# Grove_-_Serial_MP3_Player.net
KiCad netlist of a schematic drawn in EAGLE
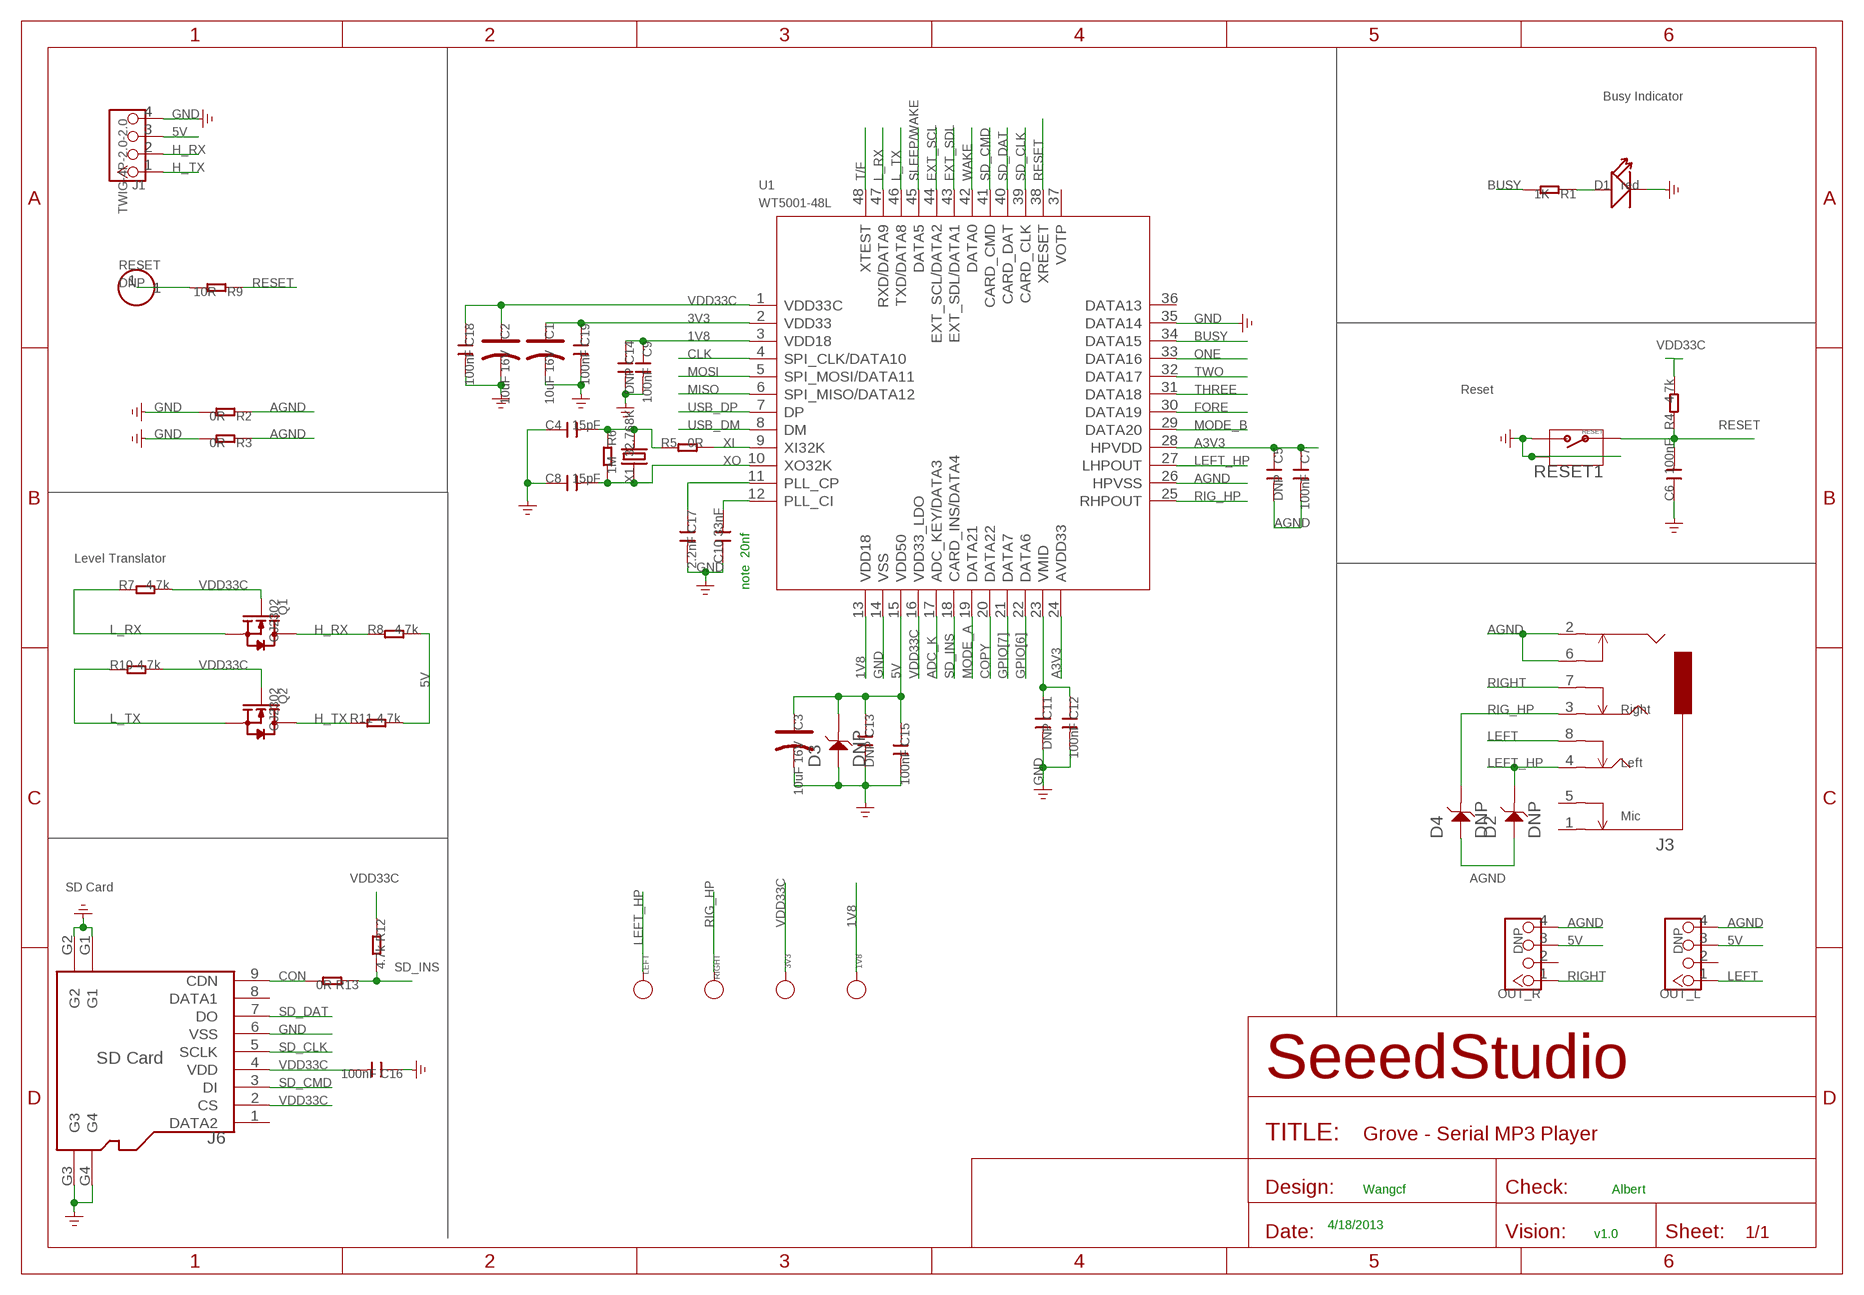
[diagram p0: schematic, sheet 1]

(export (version "E")
  (design (tool "Eeschema 10.0.6"))
  (components
    (comp (ref "1V8")
      (value "PAD-TEST-POINT'4545'")
      (footprint "eagle-import:TP_4545")
      (fields (field (name "PARTNO") "DNP"))
      (libsource (lib "eagle-import") (part "PAD-TEST-POINT'4545'"))
    )
    (comp (ref "3V3")
      (value "PAD-TEST-POINT'4545'")
      (footprint "eagle-import:TP_4545")
      (fields (field (name "PARTNO") "DNP"))
      (libsource (lib "eagle-import") (part "PAD-TEST-POINT'4545'"))
    )
    (comp (ref "C1")
      (value "10uF 16V")
      (footprint "eagle-import:AVX-A")
      (libsource (lib "eagle-import") (part "CAP-AVX-A"))
    )
    (comp (ref "C2")
      (value "10uF 16V")
      (footprint "eagle-import:AVX-A")
      (libsource (lib "eagle-import") (part "CAP-AVX-A"))
    )
    (comp (ref "C3")
      (value "10uF 16V")
      (footprint "eagle-import:AVX-A")
      (libsource (lib "eagle-import") (part "CAP-AVX-A"))
    )
    (comp (ref "C4")
      (value "15pF")
      (footprint "eagle-import:C0603")
      (libsource (lib "eagle-import") (part "C-0603"))
    )
    (comp (ref "C5")
      (value "DNP")
      (footprint "eagle-import:C0805")
      (libsource (lib "eagle-import") (part "C-0805"))
    )
    (comp (ref "C6")
      (value "100nF")
      (footprint "eagle-import:C0603")
      (libsource (lib "eagle-import") (part "C-0603"))
    )
    (comp (ref "C7")
      (value "100nF")
      (footprint "eagle-import:C0603")
      (libsource (lib "eagle-import") (part "C-0603"))
    )
    (comp (ref "C8")
      (value "15pF")
      (footprint "eagle-import:C0603")
      (libsource (lib "eagle-import") (part "C-0603"))
    )
    (comp (ref "C9")
      (value "100nF")
      (footprint "eagle-import:C0603")
      (libsource (lib "eagle-import") (part "C-0603"))
    )
    (comp (ref "C10")
      (value "33nF")
      (footprint "eagle-import:C0603")
      (libsource (lib "eagle-import") (part "C-0603"))
    )
    (comp (ref "C11")
      (value "DNP")
      (footprint "eagle-import:C0805")
      (libsource (lib "eagle-import") (part "C-0805"))
    )
    (comp (ref "C12")
      (value "100nF")
      (footprint "eagle-import:C0603")
      (libsource (lib "eagle-import") (part "C-0603"))
    )
    (comp (ref "C13")
      (value "DNP")
      (footprint "eagle-import:C0805")
      (libsource (lib "eagle-import") (part "C-0805"))
    )
    (comp (ref "C14")
      (value "DNP")
      (footprint "eagle-import:C0805")
      (libsource (lib "eagle-import") (part "C-0805"))
    )
    (comp (ref "C15")
      (value "100nF")
      (footprint "eagle-import:C0603")
      (libsource (lib "eagle-import") (part "C-0603"))
    )
    (comp (ref "C16")
      (value "100nF")
      (footprint "eagle-import:C0603")
      (libsource (lib "eagle-import") (part "C-0603"))
    )
    (comp (ref "C17")
      (value "2.2nF")
      (footprint "eagle-import:C0603")
      (libsource (lib "eagle-import") (part "C-0603"))
    )
    (comp (ref "C18")
      (value "100nF")
      (footprint "eagle-import:C0603")
      (libsource (lib "eagle-import") (part "C-0603"))
    )
    (comp (ref "C19")
      (value "100nF")
      (footprint "eagle-import:C0603")
      (libsource (lib "eagle-import") (part "C-0603"))
    )
    (comp (ref "D1")
      (value "red")
      (footprint "eagle-import:LED-0603")
      (libsource (lib "eagle-import") (part "LED'0603'"))
    )
    (comp (ref "D2")
      (value "DNP")
      (footprint "eagle-import:SOD123-2.7X1.6")
      (libsource (lib "eagle-import") (part "D-ESD-2P'CESD5V0D1'"))
    )
    (comp (ref "D3")
      (value "DNP")
      (footprint "eagle-import:SOD123-2.7X1.6")
      (libsource (lib "eagle-import") (part "D-ESD-2P'CESD5V0D1'"))
    )
    (comp (ref "D4")
      (value "DNP")
      (footprint "eagle-import:SOD123-2.7X1.6")
      (libsource (lib "eagle-import") (part "D-ESD-2P'CESD5V0D1'"))
    )
    (comp (ref "J1")
      (value "TWIG-4P-2.0-2.0")
      (footprint "eagle-import:4P-2.0")
      (libsource (lib "eagle-import") (part "TWIG-4P-2.0-2.0"))
    )
    (comp (ref "J3")
      (value "AUDIO-8P-SMD'PJ-3536-L6S'")
      (footprint "eagle-import:8P-3.5-SMD")
      (libsource (lib "eagle-import") (part "AUDIO-8P-SMD'PJ-3536-L6S'"))
    )
    (comp (ref "J6")
      (value "SD Card")
      (footprint "eagle-import:9P-SMD-W_-RING")
      (libsource (lib "eagle-import") (part "HOLDER-MICROSD-9P"))
    )
    (comp (ref "LEFT")
      (value "PAD-TEST-POINT'4545'")
      (footprint "eagle-import:TP_4545")
      (fields (field (name "PARTNO") "DNP"))
      (libsource (lib "eagle-import") (part "PAD-TEST-POINT'4545'"))
    )
    (comp (ref "OUT_L")
      (value "DNP")
      (footprint "eagle-import:4P-2.0")
      (libsource (lib "eagle-import") (part "TWIG-4P-2.0-2.0"))
    )
    (comp (ref "OUT_R")
      (value "DNP")
      (footprint "eagle-import:4P-2.0")
      (libsource (lib "eagle-import") (part "TWIG-4P-2.0-2.0"))
    )
    (comp (ref "Q1")
      (value "CJ2302")
      (footprint "eagle-import:SOT23")
      (libsource (lib "eagle-import") (part "MOSFET-N'SOT23'"))
    )
    (comp (ref "Q2")
      (value "CJ2302")
      (footprint "eagle-import:SOT23")
      (libsource (lib "eagle-import") (part "MOSFET-N'SOT23'"))
    )
    (comp (ref "R1")
      (value "1K")
      (footprint "eagle-import:R0603")
      (libsource (lib "eagle-import") (part "R-0603"))
    )
    (comp (ref "R2")
      (value "0R")
      (footprint "eagle-import:R0603")
      (libsource (lib "eagle-import") (part "R-0603"))
    )
    (comp (ref "R3")
      (value "0R")
      (footprint "eagle-import:R0603")
      (libsource (lib "eagle-import") (part "R-0603"))
    )
    (comp (ref "R4")
      (value "4.7k")
      (footprint "eagle-import:R0603")
      (libsource (lib "eagle-import") (part "R-0603"))
    )
    (comp (ref "R5")
      (value "0R")
      (footprint "eagle-import:R0603")
      (libsource (lib "eagle-import") (part "R-0603"))
    )
    (comp (ref "R6")
      (value "1M")
      (footprint "eagle-import:R0603")
      (libsource (lib "eagle-import") (part "R-0603"))
    )
    (comp (ref "R7")
      (value "4.7k")
      (footprint "eagle-import:R0603")
      (libsource (lib "eagle-import") (part "R-0603"))
    )
    (comp (ref "R8")
      (value "4.7k")
      (footprint "eagle-import:R0603")
      (libsource (lib "eagle-import") (part "R-0603"))
    )
    (comp (ref "R9")
      (value "10R")
      (footprint "eagle-import:R0603")
      (libsource (lib "eagle-import") (part "R-0603"))
    )
    (comp (ref "R10")
      (value "4.7k")
      (footprint "eagle-import:R0603")
      (libsource (lib "eagle-import") (part "R-0603"))
    )
    (comp (ref "R11")
      (value "4.7k")
      (footprint "eagle-import:R0603")
      (libsource (lib "eagle-import") (part "R-0603"))
    )
    (comp (ref "R12")
      (value "4.7k")
      (footprint "eagle-import:R0603")
      (libsource (lib "eagle-import") (part "R-0603"))
    )
    (comp (ref "R13")
      (value "0R")
      (footprint "eagle-import:R0603")
      (libsource (lib "eagle-import") (part "R-0603"))
    )
    (comp (ref "RESET")
      (value "DNP")
      (footprint "eagle-import:1P-65_35MIL")
      (libsource (lib "eagle-import") (part "HEADER-1P-35"))
    )
    (comp (ref "RESET1")
      (value "RESET")
      (footprint "eagle-import:4P-SMD-7X3.5X3.5H")
      (libsource (lib "eagle-import") (part "BUTTON-4P-REINFORCE'TS-1188E'"))
    )
    (comp (ref "RIGHT")
      (value "PAD-TEST-POINT'4545'")
      (footprint "eagle-import:TP_4545")
      (fields (field (name "PARTNO") "DNP"))
      (libsource (lib "eagle-import") (part "PAD-TEST-POINT'4545'"))
    )
    (comp (ref "U1")
      (value "WT5001-48L")
      (footprint "eagle-import:TQFP48")
      (libsource (lib "eagle-import") (part "WT5001-48L"))
    )
    (comp (ref "X1")
      (value "32.768K")
      (footprint "eagle-import:2P-SMD-3.2X1.5")
      (libsource (lib "eagle-import") (part "CRYSTAL-3215"))
    )
  )
  (nets
    (net (code "1") (name "/1V8") (class "Default")
      (node (ref "1V8") (pin "T") (pinfunction "T_T") (pintype "bidirectional"))
      (node (ref "C14") (pin "1") (pinfunction "1_1") (pintype "passive"))
      (node (ref "C9") (pin "1") (pinfunction "1_1") (pintype "passive"))
      (node (ref "U1") (pin "13") (pinfunction "VDD18_13") (pintype "bidirectional"))
      (node (ref "U1") (pin "3") (pinfunction "VDD18_3") (pintype "bidirectional"))
    )
    (net (code "2") (name "/3V3") (class "Default")
      (node (ref "C1") (pin "+") (pinfunction "+_+") (pintype "passive"))
      (node (ref "C19") (pin "1") (pinfunction "1_1") (pintype "passive"))
      (node (ref "U1") (pin "2") (pinfunction "VDD33_2") (pintype "bidirectional"))
    )
    (net (code "3") (name "/5V") (class "Default")
      (node (ref "C13") (pin "1") (pinfunction "1_1") (pintype "passive"))
      (node (ref "C15") (pin "1") (pinfunction "1_1") (pintype "passive"))
      (node (ref "C3") (pin "+") (pinfunction "+_+") (pintype "passive"))
      (node (ref "D3") (pin "2") (pinfunction "2_2") (pintype "bidirectional"))
      (node (ref "J1") (pin "3") (pinfunction "3_3") (pintype "bidirectional"))
      (node (ref "OUT_L") (pin "3") (pinfunction "3_3") (pintype "bidirectional"))
      (node (ref "OUT_R") (pin "3") (pinfunction "3_3") (pintype "bidirectional"))
      (node (ref "R11") (pin "2") (pinfunction "2_2") (pintype "passive"))
      (node (ref "R8") (pin "2") (pinfunction "2_2") (pintype "passive"))
      (node (ref "U1") (pin "15") (pinfunction "VDD50_15") (pintype "bidirectional"))
    )
    (net (code "4") (name "/A3V3") (class "Default")
      (node (ref "C5") (pin "1") (pinfunction "1_1") (pintype "passive"))
      (node (ref "C7") (pin "1") (pinfunction "1_1") (pintype "passive"))
      (node (ref "U1") (pin "24") (pinfunction "AVDD33_24") (pintype "bidirectional"))
      (node (ref "U1") (pin "28") (pinfunction "HPVDD_28") (pintype "bidirectional"))
    )
    (net (code "5") (name "/ADC_K") (class "Default")
      (node (ref "U1") (pin "17") (pinfunction "ADC_KEY/DATA3_17") (pintype "bidirectional"))
    )
    (net (code "6") (name "/AGND") (class "Default")
      (node (ref "C5") (pin "2") (pinfunction "2_2") (pintype "passive"))
      (node (ref "C7") (pin "2") (pinfunction "2_2") (pintype "passive"))
      (node (ref "D2") (pin "1") (pinfunction "1_1") (pintype "bidirectional"))
      (node (ref "D4") (pin "1") (pinfunction "1_1") (pintype "bidirectional"))
      (node (ref "J3") (pin "2") (pinfunction "2_2") (pintype "bidirectional"))
      (node (ref "J3") (pin "6") (pinfunction "6_6") (pintype "bidirectional"))
      (node (ref "OUT_L") (pin "4") (pinfunction "4_4") (pintype "bidirectional"))
      (node (ref "OUT_R") (pin "4") (pinfunction "4_4") (pintype "bidirectional"))
      (node (ref "R2") (pin "1") (pinfunction "1_1") (pintype "passive"))
      (node (ref "R3") (pin "1") (pinfunction "1_1") (pintype "passive"))
      (node (ref "U1") (pin "26") (pinfunction "HPVSS_26") (pintype "bidirectional"))
    )
    (net (code "7") (name "/BUSY") (class "Default")
      (node (ref "R1") (pin "2") (pinfunction "2_2") (pintype "passive"))
      (node (ref "U1") (pin "34") (pinfunction "DATA15_34") (pintype "bidirectional"))
    )
    (net (code "8") (name "/CLK") (class "Default")
      (node (ref "U1") (pin "4") (pinfunction "SPI_CLK/DATA10_4") (pintype "bidirectional"))
    )
    (net (code "9") (name "/CON") (class "Default")
      (node (ref "J6") (pin "9") (pinfunction "CDN_9") (pintype "bidirectional"))
      (node (ref "R13") (pin "2") (pinfunction "2_2") (pintype "passive"))
    )
    (net (code "10") (name "/COPY") (class "Default")
      (node (ref "U1") (pin "20") (pinfunction "DATA22_20") (pintype "bidirectional"))
    )
    (net (code "11") (name "/EXT_SCL") (class "Default")
      (node (ref "U1") (pin "44") (pinfunction "EXT_SCL/DATA2_44") (pintype "bidirectional"))
    )
    (net (code "12") (name "/EXT_SDL") (class "Default")
      (node (ref "U1") (pin "43") (pinfunction "EXT_SDL/DATA1_43") (pintype "bidirectional"))
    )
    (net (code "13") (name "/FORE") (class "Default")
      (node (ref "U1") (pin "30") (pinfunction "DATA19_30") (pintype "bidirectional"))
    )
    (net (code "14") (name "/GPIO[6]") (class "Default")
      (node (ref "U1") (pin "22") (pinfunction "DATA6_22") (pintype "bidirectional"))
    )
    (net (code "15") (name "/GPIO[7]") (class "Default")
      (node (ref "U1") (pin "21") (pinfunction "DATA7_21") (pintype "bidirectional"))
    )
    (net (code "16") (name "/H_RX") (class "Default")
      (node (ref "J1") (pin "2") (pinfunction "2_2") (pintype "bidirectional"))
      (node (ref "Q1") (pin "3") (pinfunction "D_3") (pintype "passive"))
      (node (ref "R8") (pin "1") (pinfunction "1_1") (pintype "passive"))
    )
    (net (code "17") (name "/H_TX") (class "Default")
      (node (ref "J1") (pin "1") (pinfunction "1_1") (pintype "bidirectional"))
      (node (ref "Q2") (pin "3") (pinfunction "D_3") (pintype "passive"))
      (node (ref "R11") (pin "1") (pinfunction "1_1") (pintype "passive"))
    )
    (net (code "18") (name "/LEFT") (class "Default")
      (node (ref "J3") (pin "8") (pinfunction "8_8") (pintype "bidirectional"))
      (node (ref "OUT_L") (pin "1") (pinfunction "1_1") (pintype "bidirectional"))
    )
    (net (code "19") (name "/LEFT_HP") (class "Default")
      (node (ref "D2") (pin "2") (pinfunction "2_2") (pintype "bidirectional"))
      (node (ref "J3") (pin "4") (pinfunction "4_4") (pintype "bidirectional"))
      (node (ref "LEFT") (pin "T") (pinfunction "T_T") (pintype "bidirectional"))
      (node (ref "U1") (pin "27") (pinfunction "LHPOUT_27") (pintype "bidirectional"))
    )
    (net (code "20") (name "/L_RX") (class "Default")
      (node (ref "Q1") (pin "2") (pinfunction "S_2") (pintype "passive"))
      (node (ref "R7") (pin "1") (pinfunction "1_1") (pintype "passive"))
      (node (ref "U1") (pin "47") (pinfunction "RXD/DATA9_47") (pintype "bidirectional"))
    )
    (net (code "21") (name "/L_TX") (class "Default")
      (node (ref "Q2") (pin "2") (pinfunction "S_2") (pintype "passive"))
      (node (ref "R10") (pin "1") (pinfunction "1_1") (pintype "passive"))
      (node (ref "U1") (pin "46") (pinfunction "TXD/DATA8_46") (pintype "bidirectional"))
    )
    (net (code "22") (name "/MISO") (class "Default")
      (node (ref "U1") (pin "6") (pinfunction "SPI_MISO/DATA12_6") (pintype "bidirectional"))
    )
    (net (code "23") (name "/MODE_A") (class "Default")
      (node (ref "U1") (pin "19") (pinfunction "DATA21_19") (pintype "bidirectional"))
    )
    (net (code "24") (name "/MODE_B") (class "Default")
      (node (ref "U1") (pin "29") (pinfunction "DATA20_29") (pintype "bidirectional"))
    )
    (net (code "25") (name "/MOSI") (class "Default")
      (node (ref "U1") (pin "5") (pinfunction "SPI_MOSI/DATA11_5") (pintype "bidirectional"))
    )
    (net (code "26") (name "/ONE") (class "Default")
      (node (ref "U1") (pin "33") (pinfunction "DATA16_33") (pintype "bidirectional"))
    )
    (net (code "27") (name "/RESET") (class "Default")
      (node (ref "C6") (pin "2") (pinfunction "2_2") (pintype "passive"))
      (node (ref "R4") (pin "1") (pinfunction "1_1") (pintype "passive"))
      (node (ref "R9") (pin "1") (pinfunction "1_1") (pintype "passive"))
      (node (ref "RESET1") (pin "1") (pinfunction "1_1") (pintype "bidirectional"))
      (node (ref "U1") (pin "38") (pinfunction "XRESET_38") (pintype "bidirectional"))
    )
    (net (code "28") (name "/RIGHT") (class "Default")
      (node (ref "J3") (pin "7") (pinfunction "7_7") (pintype "bidirectional"))
      (node (ref "OUT_R") (pin "1") (pinfunction "1_1") (pintype "bidirectional"))
    )
    (net (code "29") (name "/RIG_HP") (class "Default")
      (node (ref "D4") (pin "2") (pinfunction "2_2") (pintype "bidirectional"))
      (node (ref "J3") (pin "3") (pinfunction "3_3") (pintype "bidirectional"))
      (node (ref "RIGHT") (pin "T") (pinfunction "T_T") (pintype "bidirectional"))
      (node (ref "U1") (pin "25") (pinfunction "RHPOUT_25") (pintype "bidirectional"))
    )
    (net (code "30") (name "/SD_CLK") (class "Default")
      (node (ref "J6") (pin "5") (pinfunction "SCLK_5") (pintype "bidirectional"))
      (node (ref "U1") (pin "39") (pinfunction "CARD_CLK_39") (pintype "bidirectional"))
    )
    (net (code "31") (name "/SD_CMD") (class "Default")
      (node (ref "J6") (pin "3") (pinfunction "DI_3") (pintype "bidirectional"))
      (node (ref "U1") (pin "41") (pinfunction "CARD_CMD_41") (pintype "bidirectional"))
    )
    (net (code "32") (name "/SD_DAT") (class "Default")
      (node (ref "J6") (pin "7") (pinfunction "DO_7") (pintype "bidirectional"))
      (node (ref "U1") (pin "40") (pinfunction "CARD_DAT_40") (pintype "bidirectional"))
    )
    (net (code "33") (name "/SD_INS") (class "Default")
      (node (ref "R12") (pin "2") (pinfunction "2_2") (pintype "passive"))
      (node (ref "R13") (pin "1") (pinfunction "1_1") (pintype "passive"))
      (node (ref "U1") (pin "18") (pinfunction "CARD_INS/DATA4_18") (pintype "bidirectional"))
    )
    (net (code "34") (name "/SLEEP{slash}WAKE") (class "Default")
      (node (ref "U1") (pin "45") (pinfunction "DATA5_45") (pintype "bidirectional"))
    )
    (net (code "35") (name "/THREE") (class "Default")
      (node (ref "U1") (pin "31") (pinfunction "DATA18_31") (pintype "bidirectional"))
    )
    (net (code "36") (name "/TWO") (class "Default")
      (node (ref "U1") (pin "32") (pinfunction "DATA17_32") (pintype "bidirectional"))
    )
    (net (code "37") (name "/T{slash}F") (class "Default")
      (node (ref "U1") (pin "48") (pinfunction "XTEST_48") (pintype "bidirectional"))
    )
    (net (code "38") (name "/USB_DM") (class "Default")
      (node (ref "U1") (pin "8") (pinfunction "DM_8") (pintype "bidirectional"))
    )
    (net (code "39") (name "/USB_DP") (class "Default")
      (node (ref "U1") (pin "7") (pinfunction "DP_7") (pintype "bidirectional"))
    )
    (net (code "40") (name "/VDD33C") (class "Default")
      (node (ref "3V3") (pin "T") (pinfunction "T_T") (pintype "bidirectional"))
      (node (ref "C16") (pin "2") (pinfunction "2_2") (pintype "passive"))
      (node (ref "C18") (pin "1") (pinfunction "1_1") (pintype "passive"))
      (node (ref "C2") (pin "+") (pinfunction "+_+") (pintype "passive"))
      (node (ref "J6") (pin "2") (pinfunction "CS_2") (pintype "bidirectional"))
      (node (ref "J6") (pin "4") (pinfunction "VDD_4") (pintype "bidirectional"))
      (node (ref "Q1") (pin "1") (pinfunction "G_1") (pintype "passive"))
      (node (ref "Q2") (pin "1") (pinfunction "G_1") (pintype "passive"))
      (node (ref "R10") (pin "2") (pinfunction "2_2") (pintype "passive"))
      (node (ref "R12") (pin "1") (pinfunction "1_1") (pintype "passive"))
      (node (ref "R4") (pin "2") (pinfunction "2_2") (pintype "passive"))
      (node (ref "R7") (pin "2") (pinfunction "2_2") (pintype "passive"))
      (node (ref "U1") (pin "1") (pinfunction "VDD33C_1") (pintype "bidirectional"))
      (node (ref "U1") (pin "16") (pinfunction "VDD33_LDO_16") (pintype "bidirectional"))
    )
    (net (code "41") (name "/WAKE") (class "Default")
      (node (ref "U1") (pin "42") (pinfunction "DATA0_42") (pintype "bidirectional"))
    )
    (net (code "42") (name "/XI") (class "Default")
      (node (ref "R5") (pin "2") (pinfunction "2_2") (pintype "passive"))
      (node (ref "U1") (pin "9") (pinfunction "XI32K_9") (pintype "bidirectional"))
    )
    (net (code "43") (name "/XO") (class "Default")
      (node (ref "C8") (pin "2") (pinfunction "2_2") (pintype "passive"))
      (node (ref "R6") (pin "2") (pinfunction "2_2") (pintype "passive"))
      (node (ref "U1") (pin "10") (pinfunction "XO32K_10") (pintype "bidirectional"))
      (node (ref "X1") (pin "1") (pinfunction "1_1") (pintype "passive"))
    )
    (net (code "44") (name "GND_POWER") (class "Default")
      (node (ref "C1") (pin "-") (pinfunction "-_-") (pintype "passive"))
      (node (ref "C10") (pin "1") (pinfunction "1_1") (pintype "passive"))
      (node (ref "C11") (pin "2") (pinfunction "2_2") (pintype "passive"))
      (node (ref "C12") (pin "2") (pinfunction "2_2") (pintype "passive"))
      (node (ref "C13") (pin "2") (pinfunction "2_2") (pintype "passive"))
      (node (ref "C14") (pin "2") (pinfunction "2_2") (pintype "passive"))
      (node (ref "C15") (pin "2") (pinfunction "2_2") (pintype "passive"))
      (node (ref "C16") (pin "1") (pinfunction "1_1") (pintype "passive"))
      (node (ref "C17") (pin "2") (pinfunction "2_2") (pintype "passive"))
      (node (ref "C18") (pin "2") (pinfunction "2_2") (pintype "passive"))
      (node (ref "C19") (pin "2") (pinfunction "2_2") (pintype "passive"))
      (node (ref "C2") (pin "-") (pinfunction "-_-") (pintype "passive"))
      (node (ref "C3") (pin "-") (pinfunction "-_-") (pintype "passive"))
      (node (ref "C4") (pin "1") (pinfunction "1_1") (pintype "passive"))
      (node (ref "C6") (pin "1") (pinfunction "1_1") (pintype "passive"))
      (node (ref "C8") (pin "1") (pinfunction "1_1") (pintype "passive"))
      (node (ref "C9") (pin "2") (pinfunction "2_2") (pintype "passive"))
      (node (ref "D1") (pin "-") (pinfunction "-_-") (pintype "passive"))
      (node (ref "D3") (pin "1") (pinfunction "1_1") (pintype "bidirectional"))
      (node (ref "J1") (pin "4") (pinfunction "4_4") (pintype "bidirectional"))
      (node (ref "J6") (pin "6") (pinfunction "VSS_6") (pintype "bidirectional"))
      (node (ref "J6") (pin "G1") (pinfunction "G1_G1") (pintype "bidirectional"))
      (node (ref "J6") (pin "G2") (pinfunction "G2_G2") (pintype "bidirectional"))
      (node (ref "J6") (pin "G3") (pinfunction "G3_G3") (pintype "bidirectional"))
      (node (ref "J6") (pin "G4") (pinfunction "G4_G4") (pintype "bidirectional"))
      (node (ref "R2") (pin "2") (pinfunction "2_2") (pintype "passive"))
      (node (ref "R3") (pin "2") (pinfunction "2_2") (pintype "passive"))
      (node (ref "RESET1") (pin "2") (pinfunction "2_2") (pintype "bidirectional"))
      (node (ref "RESET1") (pin "S1") (pinfunction "S1_S1") (pintype "bidirectional"))
      (node (ref "RESET1") (pin "S2") (pinfunction "S2_S2") (pintype "bidirectional"))
      (node (ref "U1") (pin "14") (pinfunction "VSS_14") (pintype "bidirectional"))
      (node (ref "U1") (pin "35") (pinfunction "DATA14_35") (pintype "bidirectional"))
    )
    (net (code "45") (name "Net-(C4-Pad2)") (class "Default")
      (node (ref "C4") (pin "2") (pinfunction "2_2") (pintype "passive"))
      (node (ref "R5") (pin "1") (pinfunction "1_1") (pintype "passive"))
      (node (ref "R6") (pin "1") (pinfunction "1_1") (pintype "passive"))
      (node (ref "X1") (pin "2") (pinfunction "2_2") (pintype "passive"))
    )
    (net (code "46") (name "Net-(D1-Pad+)") (class "Default")
      (node (ref "D1") (pin "+") (pinfunction "+_+") (pintype "passive"))
      (node (ref "R1") (pin "1") (pinfunction "1_1") (pintype "passive"))
    )
    (net (code "47") (name "Net-(R9-Pad2)") (class "Default")
      (node (ref "R9") (pin "2") (pinfunction "2_2") (pintype "passive"))
      (node (ref "RESET") (pin "1") (pinfunction "1_1") (pintype "bidirectional"))
    )
    (net (code "48") (name "Net-(U1-PLL_CI)") (class "Default")
      (node (ref "C10") (pin "2") (pinfunction "2_2") (pintype "passive"))
      (node (ref "U1") (pin "12") (pinfunction "PLL_CI_12") (pintype "bidirectional"))
    )
    (net (code "49") (name "Net-(U1-PLL_CP)") (class "Default")
      (node (ref "C17") (pin "1") (pinfunction "1_1") (pintype "passive"))
      (node (ref "U1") (pin "11") (pinfunction "PLL_CP_11") (pintype "bidirectional"))
    )
    (net (code "50") (name "Net-(U1-VMID)") (class "Default")
      (node (ref "C11") (pin "1") (pinfunction "1_1") (pintype "passive"))
      (node (ref "C12") (pin "1") (pinfunction "1_1") (pintype "passive"))
      (node (ref "U1") (pin "23") (pinfunction "VMID_23") (pintype "bidirectional"))
    )
    (net (code "51") (name "unconnected-(J3-Pad1)") (class "Default")
      (node (ref "J3") (pin "1") (pinfunction "1_1") (pintype "bidirectional"))
    )
    (net (code "52") (name "unconnected-(J3-Pad5)") (class "Default")
      (node (ref "J3") (pin "5") (pinfunction "5_5") (pintype "bidirectional"))
    )
    (net (code "53") (name "unconnected-(J6-DATA1-Pad8)") (class "Default")
      (node (ref "J6") (pin "8") (pinfunction "DATA1_8") (pintype "bidirectional"))
    )
    (net (code "54") (name "unconnected-(J6-DATA2-Pad1)") (class "Default")
      (node (ref "J6") (pin "1") (pinfunction "DATA2_1") (pintype "bidirectional"))
    )
    (net (code "55") (name "unconnected-(OUT_L-Pad2)") (class "Default")
      (node (ref "OUT_L") (pin "2") (pinfunction "2_2") (pintype "bidirectional"))
    )
    (net (code "56") (name "unconnected-(OUT_R-Pad2)") (class "Default")
      (node (ref "OUT_R") (pin "2") (pinfunction "2_2") (pintype "bidirectional"))
    )
    (net (code "57") (name "unconnected-(U1-DATA13-Pad36)") (class "Default")
      (node (ref "U1") (pin "36") (pinfunction "DATA13_36") (pintype "bidirectional"))
    )
    (net (code "58") (name "unconnected-(U1-VOTP-Pad37)") (class "Default")
      (node (ref "U1") (pin "37") (pinfunction "VOTP_37") (pintype "bidirectional"))
    )
  )
)
